# TSOC_GROVEY_WIFI_R1_1.net
KiCad netlist of a schematic drawn in EAGLE
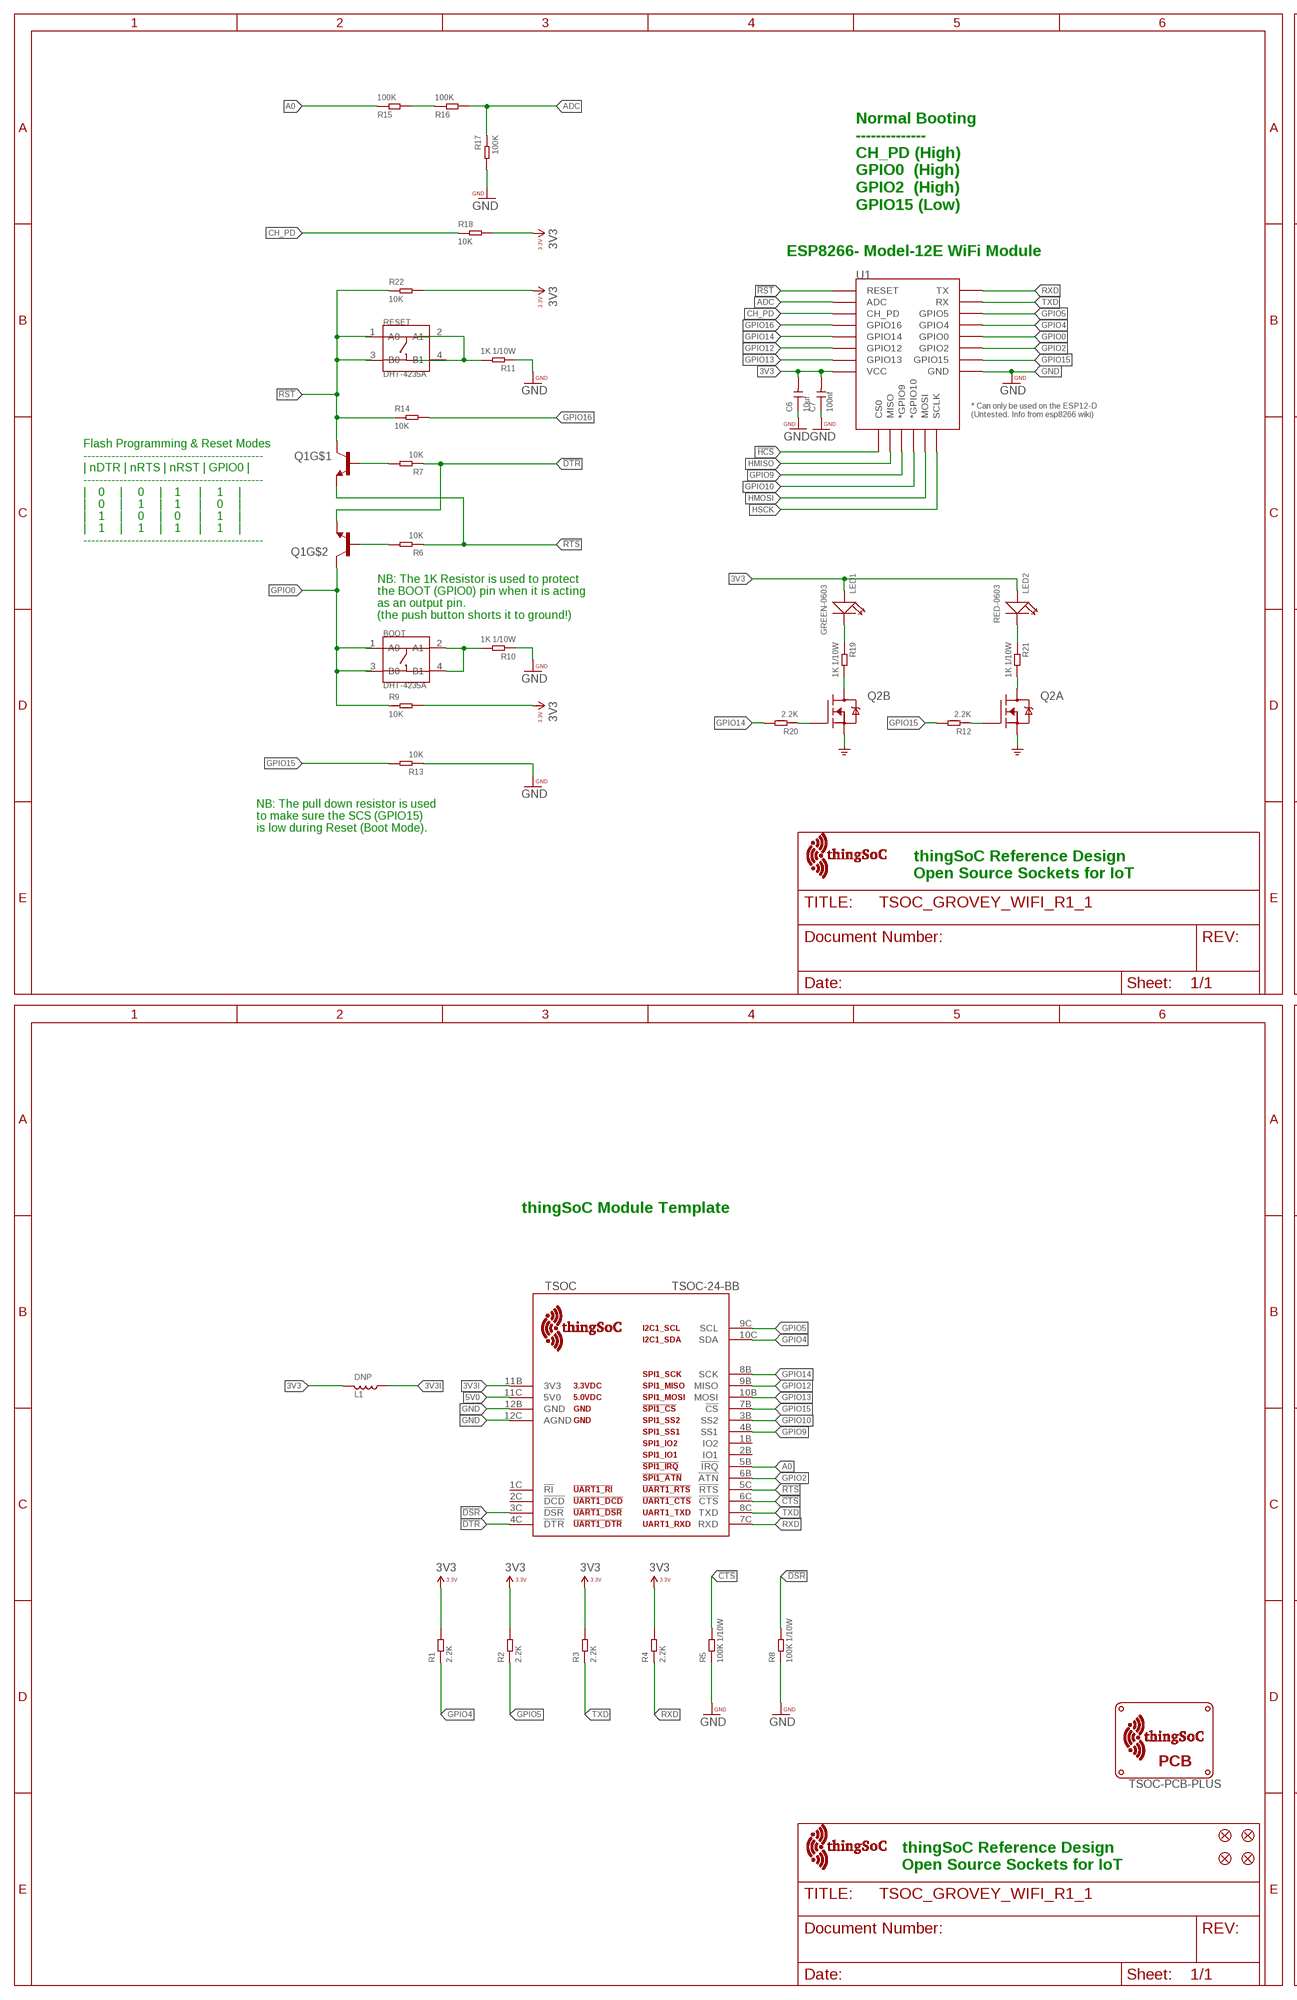
[diagram p0: schematic, sheet 1, part 1 of 2]
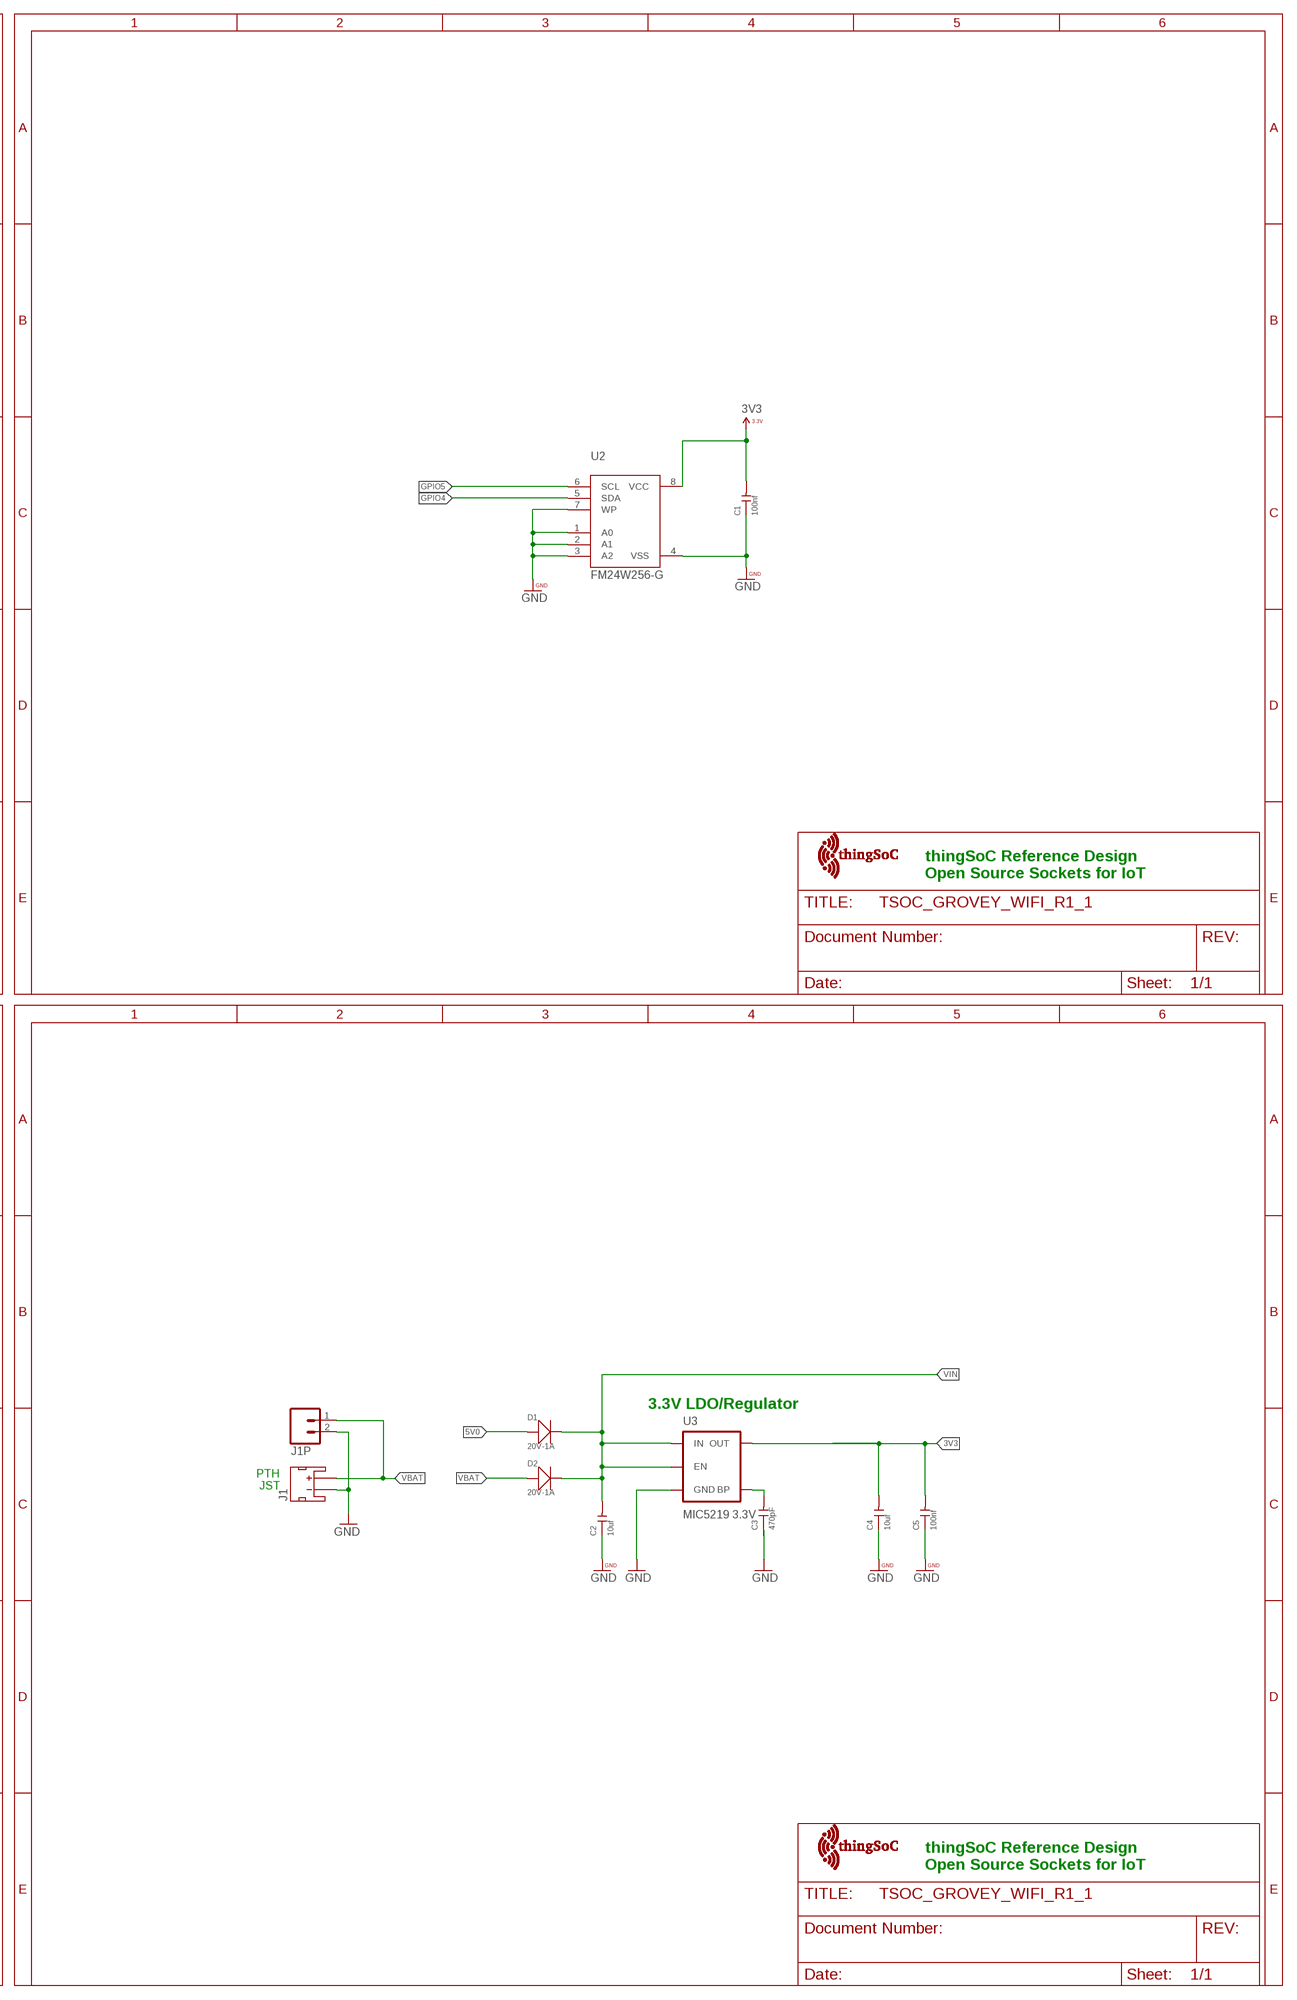
[diagram p1: schematic, sheet 1, part 2 of 2]

(export (version "E")
  (design (tool "Eeschema 10.0.6"))
  (components
    (comp (ref "$$U$1")
      (value "TSOC-LOGO-MED")
      (footprint "eagle-import:TSOC-LOGO-MED")
      (libsource (lib "eagle-import") (part "TSOC-LOGO-MED"))
    )
    (comp (ref "$$U$2")
      (value "TSOC-LOGO-MED")
      (footprint "eagle-import:TSOC-LOGO-MED")
      (libsource (lib "eagle-import") (part "TSOC-LOGO-MED"))
    )
    (comp (ref "BOOT")
      (value "DHT-4235A")
      (footprint "eagle-import:SW4-SMD-4.2X3.2X2.5MM")
      (libsource (lib "eagle-import") (part "SMD-BUTTON-TOP-DHT-4235A(4P-4.2X3.2MM)"))
    )
    (comp (ref "C1")
      (value "100nf")
      (footprint "eagle-import:C0603")
      (fields (field (name "MPN") "CC0603KRX7R9BB104"))
      (libsource (lib "eagle-import") (part "CERAMIC-100NF-50V-10%-X7R(0603)"))
    )
    (comp (ref "C2")
      (value "10uf")
      (footprint "eagle-import:C1206")
      (fields (field (name "MPN") "CC1206KKX5R8BB106"))
      (libsource (lib "eagle-import") (part "CERAMIC-10UF-25V-10%-X5R(1206)"))
    )
    (comp (ref "C3")
      (value "470pF")
      (footprint "eagle-import:C0603")
      (fields (field (name "MPN") "CC0603KRX7R9BB104"))
      (libsource (lib "eagle-import") (part "CERAMIC-100NF-50V-10%-X7R(0603)"))
    )
    (comp (ref "C4")
      (value "10uf")
      (footprint "eagle-import:C1206")
      (fields (field (name "MPN") "CC1206KKX5R8BB106"))
      (libsource (lib "eagle-import") (part "CERAMIC-10UF-25V-10%-X5R(1206)"))
    )
    (comp (ref "C5")
      (value "100nf")
      (footprint "eagle-import:C0603")
      (fields (field (name "MPN") "CC0603KRX7R9BB104"))
      (libsource (lib "eagle-import") (part "CERAMIC-100NF-50V-10%-X7R(0603)"))
    )
    (comp (ref "C6")
      (value "10uf")
      (footprint "eagle-import:C1206")
      (fields (field (name "MPN") "CC1206KKX5R8BB106"))
      (libsource (lib "eagle-import") (part "CERAMIC-10UF-25V-10%-X5R(1206)"))
    )
    (comp (ref "C7")
      (value "100nf")
      (footprint "eagle-import:C0603")
      (fields (field (name "MPN") "CC0603KRX7R9BB104"))
      (libsource (lib "eagle-import") (part "CERAMIC-100NF-50V-10%-X7R(0603)"))
    )
    (comp (ref "D1")
      (value "20V-1A")
      (footprint "eagle-import:SOD-123")
      (fields (field (name "MPN") "B5819W"))
      (libsource (lib "eagle-import") (part "SMD-DIODE-SCHOTTKY-20V-1A(SOD-123)"))
    )
    (comp (ref "D2")
      (value "20V-1A")
      (footprint "eagle-import:SOD-123")
      (fields (field (name "MPN") "B5819W"))
      (libsource (lib "eagle-import") (part "SMD-DIODE-SCHOTTKY-20V-1A(SOD-123)"))
    )
    (comp (ref "FID1")
      (value "FIDUCIALUFIDUCIAL")
      (footprint "eagle-import:MICRO-FIDUCIAL")
      (libsource (lib "eagle-import") (part "FIDUCIALUFIDUCIAL"))
    )
    (comp (ref "FID2")
      (value "FIDUCIALUFIDUCIAL")
      (footprint "eagle-import:MICRO-FIDUCIAL")
      (libsource (lib "eagle-import") (part "FIDUCIALUFIDUCIAL"))
    )
    (comp (ref "FID3")
      (value "FIDUCIALUFIDUCIAL")
      (footprint "eagle-import:MICRO-FIDUCIAL")
      (libsource (lib "eagle-import") (part "FIDUCIALUFIDUCIAL"))
    )
    (comp (ref "FID4")
      (value "FIDUCIALUFIDUCIAL")
      (footprint "eagle-import:MICRO-FIDUCIAL")
      (libsource (lib "eagle-import") (part "FIDUCIALUFIDUCIAL"))
    )
    (comp (ref "J1")
      (value "JST_2MM_MALE")
      (footprint "eagle-import:JST-2-SMD")
      (libsource (lib "eagle-import") (part "JST_2MM_MALE"))
    )
    (comp (ref "J1P")
      (value "M02-JST-2-PTH-NO_SILK")
      (footprint "eagle-import:JST-2-PTH-NS")
      (libsource (lib "eagle-import") (part "M02-JST-2-PTH-NO_SILK"))
    )
    (comp (ref "L1")
      (value "DNP")
      (footprint "eagle-import:L0603")
      (fields (field (name "MPN") "BLM18AG121SN1D"))
      (libsource (lib "eagle-import") (part "SMD-FERRITE-CHIP-120-OHM-500MA(0603)"))
    )
    (comp (ref "LED1")
      (value "GREEN-0603")
      (footprint "eagle-import:LED-0603")
      (fields (field (name "MPN") "19-217-G7C-AN1P2-3T"))
      (libsource (lib "eagle-import") (part "SMD-LED-CLEAR-GREEN(0603)"))
    )
    (comp (ref "LED2")
      (value "RED-0603")
      (footprint "eagle-import:LED-0603")
      (fields (field (name "MPN") "19-217-R6C-AL1M2VY-3T"))
      (libsource (lib "eagle-import") (part "LED-SMD-RED-DIFFUSED(0603)"))
    )
    (comp (ref "PCB")
      (value "TSOC-PCB-PLUS")
      (footprint "eagle-import:TSOC-BB-BRD-PLUS-DIM")
      (libsource (lib "eagle-import") (part "TSOC-PCB-PLUS"))
    )
    (comp (ref "Q1")
      (value "MMBT2222A")
      (footprint "eagle-import:SOT363")
      (libsource (lib "eagle-import") (part "MMDT3904"))
    )
    (comp (ref "Q2")
      (value "FDG1024NZ")
      (footprint "eagle-import:SOT95P280X110-6N")
      (libsource (lib "eagle-import") (part "FDG1024NZ"))
    )
    (comp (ref "R1")
      (value "2.2K")
      (footprint "eagle-import:R0603")
      (fields (field (name "MPN") "RC0603JR-072K2L"))
      (libsource (lib "eagle-import") (part "SMD-RES-2.2K-5%-1/10W(0603)"))
    )
    (comp (ref "R2")
      (value "2.2K")
      (footprint "eagle-import:R0603")
      (fields (field (name "MPN") "RC0603JR-072K2L"))
      (libsource (lib "eagle-import") (part "SMD-RES-2.2K-5%-1/10W(0603)"))
    )
    (comp (ref "R3")
      (value "2.2K")
      (footprint "eagle-import:R0603")
      (fields (field (name "MPN") "RC0603JR-072K2L"))
      (libsource (lib "eagle-import") (part "SMD-RES-2.2K-5%-1/10W(0603)"))
    )
    (comp (ref "R4")
      (value "2.2K")
      (footprint "eagle-import:R0603")
      (fields (field (name "MPN") "RC0603JR-072K2L"))
      (libsource (lib "eagle-import") (part "SMD-RES-2.2K-5%-1/10W(0603)"))
    )
    (comp (ref "R5")
      (value "100K 1/10W")
      (footprint "eagle-import:R0603")
      (fields (field (name "MPN") "RC0603JR-07100KL"))
      (libsource (lib "eagle-import") (part "SMD-RES-100K-5%-1/10W(0603)"))
    )
    (comp (ref "R6")
      (value "10K")
      (footprint "eagle-import:R0603")
      (fields (field (name "MPN") "RC0603FR-0710KL"))
      (libsource (lib "eagle-import") (part "SMD-RES-10K-1%-1/10W(0603)"))
    )
    (comp (ref "R7")
      (value "10K")
      (footprint "eagle-import:R0603")
      (fields (field (name "MPN") "RC0603FR-0710KL"))
      (libsource (lib "eagle-import") (part "SMD-RES-10K-1%-1/10W(0603)"))
    )
    (comp (ref "R8")
      (value "100K 1/10W")
      (footprint "eagle-import:R0603")
      (fields (field (name "MPN") "RC0603JR-07100KL"))
      (libsource (lib "eagle-import") (part "SMD-RES-100K-5%-1/10W(0603)"))
    )
    (comp (ref "R9")
      (value "10K")
      (footprint "eagle-import:R0603")
      (fields (field (name "MPN") "RC0603FR-0710KL"))
      (libsource (lib "eagle-import") (part "SMD-RES-10K-1%-1/10W(0603)"))
    )
    (comp (ref "R10")
      (value "1K 1/10W")
      (footprint "eagle-import:R0603")
      (fields (field (name "MPN") "RC0603JR-071KL"))
      (libsource (lib "eagle-import") (part "SMD-RES-1K-5%-1/10W(0603)"))
    )
    (comp (ref "R11")
      (value "1K 1/10W")
      (footprint "eagle-import:R0603")
      (fields (field (name "MPN") "RC0603JR-071KL"))
      (libsource (lib "eagle-import") (part "SMD-RES-1K-5%-1/10W(0603)"))
    )
    (comp (ref "R12")
      (value "2.2K")
      (footprint "eagle-import:R0603")
      (fields (field (name "MPN") "RC0603JR-072K2L"))
      (libsource (lib "eagle-import") (part "SMD-RES-2.2K-5%-1/10W(0603)"))
    )
    (comp (ref "R13")
      (value "10K")
      (footprint "eagle-import:R0603")
      (fields (field (name "MPN") "RC0603FR-0710KL"))
      (libsource (lib "eagle-import") (part "SMD-RES-10K-1%-1/10W(0603)"))
    )
    (comp (ref "R14")
      (value "10K")
      (footprint "eagle-import:R0603")
      (fields (field (name "MPN") "RC0603FR-0710KL"))
      (libsource (lib "eagle-import") (part "SMD-RES-10K-1%-1/10W(0603)"))
    )
    (comp (ref "R15")
      (value "100K")
      (footprint "eagle-import:R0603")
      (fields (field (name "MPN") "RC0603FR-07100KL"))
      (libsource (lib "eagle-import") (part "SMD-RES-100K-1%-1/10W(0603)"))
    )
    (comp (ref "R16")
      (value "100K")
      (footprint "eagle-import:R0603")
      (fields (field (name "MPN") "RC0603FR-07100KL"))
      (libsource (lib "eagle-import") (part "SMD-RES-100K-1%-1/10W(0603)"))
    )
    (comp (ref "R17")
      (value "100K")
      (footprint "eagle-import:R0603")
      (fields (field (name "MPN") "RC0603FR-07100KL"))
      (libsource (lib "eagle-import") (part "SMD-RES-100K-1%-1/10W(0603)"))
    )
    (comp (ref "R18")
      (value "10K")
      (footprint "eagle-import:R0603")
      (fields (field (name "MPN") "RC0603FR-0710KL"))
      (libsource (lib "eagle-import") (part "SMD-RES-10K-1%-1/10W(0603)"))
    )
    (comp (ref "R19")
      (value "1K 1/10W")
      (footprint "eagle-import:R0603")
      (fields (field (name "MPN") "RC0603JR-071KL"))
      (libsource (lib "eagle-import") (part "SMD-RES-1K-5%-1/10W(0603)"))
    )
    (comp (ref "R20")
      (value "2.2K")
      (footprint "eagle-import:R0603")
      (fields (field (name "MPN") "RC0603JR-072K2L"))
      (libsource (lib "eagle-import") (part "SMD-RES-2.2K-5%-1/10W(0603)"))
    )
    (comp (ref "R21")
      (value "1K 1/10W")
      (footprint "eagle-import:R0603")
      (fields (field (name "MPN") "RC0603JR-071KL"))
      (libsource (lib "eagle-import") (part "SMD-RES-1K-5%-1/10W(0603)"))
    )
    (comp (ref "R22")
      (value "10K")
      (footprint "eagle-import:R0603")
      (fields (field (name "MPN") "RC0603FR-0710KL"))
      (libsource (lib "eagle-import") (part "SMD-RES-10K-1%-1/10W(0603)"))
    )
    (comp (ref "RESET")
      (value "DHT-4235A")
      (footprint "eagle-import:SW4-SMD-4.2X3.2X2.5MM")
      (libsource (lib "eagle-import") (part "SMD-BUTTON-TOP-DHT-4235A(4P-4.2X3.2MM)"))
    )
    (comp (ref "TSOC")
      (value "TSOC-24-BB")
      (footprint "eagle-import:TSOC-BB-S24")
      (libsource (lib "eagle-import") (part "TSOC-24-BB"))
    )
    (comp (ref "U$101")
      (value "TSOC-LOGO-MED")
      (footprint "eagle-import:TSOC-LOGO-MED")
      (libsource (lib "eagle-import") (part "TSOC-LOGO-MED"))
    )
    (comp (ref "U$102")
      (value "TSOC-LOGO-MED")
      (footprint "eagle-import:TSOC-LOGO-MED")
      (libsource (lib "eagle-import") (part "TSOC-LOGO-MED"))
    )
    (comp (ref "U1")
      (value "ESP12ESMD")
      (footprint "eagle-import:ESP12E-SMD")
      (libsource (lib "eagle-import") (part "ESP12ESMD"))
    )
    (comp (ref "U2")
      (value "FM24W256-G")
      (footprint "eagle-import:SO08")
      (libsource (lib "eagle-import") (part "FM24W256-G"))
    )
    (comp (ref "U3")
      (value "MIC5219 3.3V")
      (footprint "eagle-import:SOT23-5")
      (libsource (lib "eagle-import") (part "V_REG_MIC52193.3V"))
    )
  )
  (nets
    (net (code "1") (name "/~{CTS}") (class "Default")
      (node (ref "R5") (pin "2") (pinfunction "2_2") (pintype "passive"))
      (node (ref "TSOC") (pin "6C") (pinfunction "~{CTS}_6C") (pintype "bidirectional"))
    )
    (net (code "2") (name "/~{DSR}") (class "Default")
      (node (ref "R8") (pin "2") (pinfunction "2_2") (pintype "passive"))
      (node (ref "TSOC") (pin "3C") (pinfunction "~{DSR}_3C") (pintype "bidirectional"))
    )
    (net (code "3") (name "/~{DTR}") (class "Default")
      (node (ref "Q1") (pin "1") (pinfunction "E_1") (pintype "passive"))
      (node (ref "R7") (pin "1") (pinfunction "1_1") (pintype "passive"))
      (node (ref "TSOC") (pin "4C") (pinfunction "~{DTR}_4C") (pintype "bidirectional"))
    )
    (net (code "4") (name "/~{HCS}") (class "Default")
      (node (ref "U1") (pin "CS0") (pinfunction "CS0_CS0") (pintype "bidirectional"))
    )
    (net (code "5") (name "/~{RST}") (class "Default")
      (node (ref "Q1") (pin "3") (pinfunction "C_3") (pintype "passive"))
      (node (ref "R14") (pin "1") (pinfunction "1_1") (pintype "passive"))
      (node (ref "R22") (pin "1") (pinfunction "1_1") (pintype "passive"))
      (node (ref "RESET") (pin "1") (pinfunction "A0_1") (pintype "bidirectional"))
      (node (ref "RESET") (pin "3") (pinfunction "B0_3") (pintype "bidirectional"))
      (node (ref "U1") (pin "RESET") (pinfunction "RESET_RESET") (pintype "bidirectional"))
    )
    (net (code "6") (name "/~{RTS}") (class "Default")
      (node (ref "Q1") (pin "4") (pinfunction "E_4") (pintype "passive"))
      (node (ref "R6") (pin "1") (pinfunction "1_1") (pintype "passive"))
      (node (ref "TSOC") (pin "5C") (pinfunction "~{RTS}_5C") (pintype "bidirectional"))
    )
    (net (code "7") (name "3V3") (class "Default")
      (node (ref "C1") (pin "2") (pinfunction "2_2") (pintype "passive"))
      (node (ref "C4") (pin "2") (pinfunction "2_2") (pintype "passive"))
      (node (ref "C5") (pin "2") (pinfunction "2_2") (pintype "passive"))
      (node (ref "C6") (pin "2") (pinfunction "2_2") (pintype "passive"))
      (node (ref "C7") (pin "2") (pinfunction "2_2") (pintype "passive"))
      (node (ref "L1") (pin "1") (pinfunction "1_1") (pintype "passive"))
      (node (ref "LED1") (pin "+") (pinfunction "+_+") (pintype "passive"))
      (node (ref "LED2") (pin "+") (pinfunction "+_+") (pintype "passive"))
      (node (ref "R1") (pin "2") (pinfunction "2_2") (pintype "passive"))
      (node (ref "R18") (pin "2") (pinfunction "2_2") (pintype "passive"))
      (node (ref "R2") (pin "2") (pinfunction "2_2") (pintype "passive"))
      (node (ref "R22") (pin "2") (pinfunction "2_2") (pintype "passive"))
      (node (ref "R3") (pin "2") (pinfunction "2_2") (pintype "passive"))
      (node (ref "R4") (pin "2") (pinfunction "2_2") (pintype "passive"))
      (node (ref "R9") (pin "2") (pinfunction "2_2") (pintype "passive"))
      (node (ref "U1") (pin "VCC") (pinfunction "VCC_VCC") (pintype "bidirectional"))
      (node (ref "U2") (pin "8") (pinfunction "VCC_8") (pintype "power_in"))
      (node (ref "U3") (pin "5") (pinfunction "OUT_5") (pintype "passive"))
    )
    (net (code "8") (name "3V3I") (class "Default")
      (node (ref "L1") (pin "2") (pinfunction "2_2") (pintype "passive"))
      (node (ref "TSOC") (pin "11B") (pinfunction "3V3_11B") (pintype "bidirectional"))
    )
    (net (code "9") (name "5V0") (class "Default")
      (node (ref "D1") (pin "+") (pinfunction "+_+") (pintype "passive"))
      (node (ref "TSOC") (pin "11C") (pinfunction "5V0_11C") (pintype "bidirectional"))
    )
    (net (code "10") (name "A0") (class "Default")
      (node (ref "R15") (pin "1") (pinfunction "1_1") (pintype "passive"))
      (node (ref "TSOC") (pin "5B") (pinfunction "~{IRQ}_5B") (pintype "bidirectional"))
    )
    (net (code "11") (name "ADC") (class "Default")
      (node (ref "R16") (pin "2") (pinfunction "2_2") (pintype "passive"))
      (node (ref "R17") (pin "1") (pinfunction "1_1") (pintype "passive"))
      (node (ref "U1") (pin "ADC") (pinfunction "ADC_ADC") (pintype "bidirectional"))
    )
    (net (code "12") (name "CH_PD") (class "Default")
      (node (ref "R18") (pin "1") (pinfunction "1_1") (pintype "passive"))
      (node (ref "U1") (pin "CH_PD") (pinfunction "CH_PD_CH_PD") (pintype "bidirectional"))
    )
    (net (code "13") (name "GND") (class "Default")
      (node (ref "C1") (pin "1") (pinfunction "1_1") (pintype "passive"))
      (node (ref "C2") (pin "1") (pinfunction "1_1") (pintype "passive"))
      (node (ref "C3") (pin "1") (pinfunction "1_1") (pintype "passive"))
      (node (ref "C4") (pin "1") (pinfunction "1_1") (pintype "passive"))
      (node (ref "C5") (pin "1") (pinfunction "1_1") (pintype "passive"))
      (node (ref "C6") (pin "1") (pinfunction "1_1") (pintype "passive"))
      (node (ref "C7") (pin "1") (pinfunction "1_1") (pintype "passive"))
      (node (ref "J1") (pin "1") (pinfunction "-_1") (pintype "bidirectional"))
      (node (ref "J1P") (pin "2") (pinfunction "2_2") (pintype "passive"))
      (node (ref "Q2") (pin "1") (pinfunction "S_1") (pintype "passive"))
      (node (ref "Q2") (pin "4") (pinfunction "S_4") (pintype "passive"))
      (node (ref "R10") (pin "1") (pinfunction "1_1") (pintype "passive"))
      (node (ref "R11") (pin "1") (pinfunction "1_1") (pintype "passive"))
      (node (ref "R13") (pin "1") (pinfunction "1_1") (pintype "passive"))
      (node (ref "R17") (pin "2") (pinfunction "2_2") (pintype "passive"))
      (node (ref "R5") (pin "1") (pinfunction "1_1") (pintype "passive"))
      (node (ref "R8") (pin "1") (pinfunction "1_1") (pintype "passive"))
      (node (ref "TSOC") (pin "12B") (pinfunction "GND_12B") (pintype "bidirectional"))
      (node (ref "TSOC") (pin "12C") (pinfunction "AGND_12C") (pintype "bidirectional"))
      (node (ref "U1") (pin "GND") (pinfunction "GND_GND") (pintype "bidirectional"))
      (node (ref "U2") (pin "1") (pinfunction "A0_1") (pintype "bidirectional"))
      (node (ref "U2") (pin "2") (pinfunction "A1_2") (pintype "bidirectional"))
      (node (ref "U2") (pin "3") (pinfunction "A2_3") (pintype "bidirectional"))
      (node (ref "U2") (pin "4") (pinfunction "VSS_4") (pintype "power_in"))
      (node (ref "U2") (pin "7") (pinfunction "WP_7") (pintype "bidirectional"))
      (node (ref "U3") (pin "2") (pinfunction "GND_2") (pintype "input"))
    )
    (net (code "14") (name "GPIO0") (class "Default")
      (node (ref "BOOT") (pin "1") (pinfunction "A0_1") (pintype "bidirectional"))
      (node (ref "BOOT") (pin "3") (pinfunction "B0_3") (pintype "bidirectional"))
      (node (ref "Q1") (pin "6") (pinfunction "C_6") (pintype "passive"))
      (node (ref "R9") (pin "1") (pinfunction "1_1") (pintype "passive"))
      (node (ref "U1") (pin "GPIO0") (pinfunction "GPIO0_GPIO0") (pintype "bidirectional"))
    )
    (net (code "15") (name "GPIO2") (class "Default")
      (node (ref "TSOC") (pin "6B") (pinfunction "~{ATN}_6B") (pintype "bidirectional"))
      (node (ref "U1") (pin "GPIO2") (pinfunction "GPIO2_GPIO2") (pintype "bidirectional"))
    )
    (net (code "16") (name "GPIO4") (class "Default")
      (node (ref "R1") (pin "1") (pinfunction "1_1") (pintype "passive"))
      (node (ref "TSOC") (pin "10C") (pinfunction "SDA_10C") (pintype "bidirectional"))
      (node (ref "U1") (pin "GPIO4") (pinfunction "GPIO4_GPIO4") (pintype "bidirectional"))
      (node (ref "U2") (pin "5") (pinfunction "SDA_5") (pintype "bidirectional"))
    )
    (net (code "17") (name "GPIO5") (class "Default")
      (node (ref "R2") (pin "1") (pinfunction "1_1") (pintype "passive"))
      (node (ref "TSOC") (pin "9C") (pinfunction "SCL_9C") (pintype "bidirectional"))
      (node (ref "U1") (pin "GPIO5") (pinfunction "GPIO5_GPIO5") (pintype "bidirectional"))
      (node (ref "U2") (pin "6") (pinfunction "SCL_6") (pintype "bidirectional"))
    )
    (net (code "18") (name "GPIO9") (class "Default")
      (node (ref "TSOC") (pin "4B") (pinfunction "SS1_4B") (pintype "bidirectional"))
      (node (ref "U1") (pin "GPIO9") (pinfunction "*GPIO9_GPIO9") (pintype "bidirectional"))
    )
    (net (code "19") (name "GPIO10") (class "Default")
      (node (ref "TSOC") (pin "3B") (pinfunction "SS2_3B") (pintype "bidirectional"))
      (node (ref "U1") (pin "GPIO10") (pinfunction "*GPIO10_GPIO10") (pintype "bidirectional"))
    )
    (net (code "20") (name "GPIO12") (class "Default")
      (node (ref "TSOC") (pin "9B") (pinfunction "MISO_9B") (pintype "bidirectional"))
      (node (ref "U1") (pin "GPIO12") (pinfunction "GPIO12_GPIO12") (pintype "bidirectional"))
    )
    (net (code "21") (name "GPIO13") (class "Default")
      (node (ref "TSOC") (pin "10B") (pinfunction "MOSI_10B") (pintype "bidirectional"))
      (node (ref "U1") (pin "GPIO13") (pinfunction "GPIO13_GPIO13") (pintype "bidirectional"))
    )
    (net (code "22") (name "GPIO14") (class "Default")
      (node (ref "R20") (pin "2") (pinfunction "2_2") (pintype "passive"))
      (node (ref "TSOC") (pin "8B") (pinfunction "SCK_8B") (pintype "bidirectional"))
      (node (ref "U1") (pin "GPIO14") (pinfunction "GPIO14_GPIO14") (pintype "bidirectional"))
    )
    (net (code "23") (name "GPIO15") (class "Default")
      (node (ref "R12") (pin "2") (pinfunction "2_2") (pintype "passive"))
      (node (ref "R13") (pin "2") (pinfunction "2_2") (pintype "passive"))
      (node (ref "TSOC") (pin "7B") (pinfunction "~{CS}_7B") (pintype "bidirectional"))
      (node (ref "U1") (pin "GPIO15") (pinfunction "GPIO15_GPIO15") (pintype "bidirectional"))
    )
    (net (code "24") (name "GPIO16") (class "Default")
      (node (ref "R14") (pin "2") (pinfunction "2_2") (pintype "passive"))
      (node (ref "U1") (pin "GPIO16") (pinfunction "GPIO16_GPIO16") (pintype "bidirectional"))
    )
    (net (code "25") (name "HMISO") (class "Default")
      (node (ref "U1") (pin "MISO") (pinfunction "MISO_MISO") (pintype "bidirectional"))
    )
    (net (code "26") (name "HMOSI") (class "Default")
      (node (ref "U1") (pin "MOSI") (pinfunction "MOSI_MOSI") (pintype "bidirectional"))
    )
    (net (code "27") (name "HSCK") (class "Default")
      (node (ref "U1") (pin "SCLK") (pinfunction "SCLK_SCLK") (pintype "bidirectional"))
    )
    (net (code "28") (name "Net-(BOOT-A1)") (class "Default")
      (node (ref "BOOT") (pin "2") (pinfunction "A1_2") (pintype "bidirectional"))
      (node (ref "BOOT") (pin "4") (pinfunction "B1_4") (pintype "bidirectional"))
      (node (ref "R10") (pin "2") (pinfunction "2_2") (pintype "passive"))
    )
    (net (code "29") (name "Net-(LED1-Pad-)") (class "Default")
      (node (ref "LED1") (pin "-") (pinfunction "-_-") (pintype "passive"))
      (node (ref "R19") (pin "1") (pinfunction "1_1") (pintype "passive"))
    )
    (net (code "30") (name "Net-(LED2-Pad-)") (class "Default")
      (node (ref "LED2") (pin "-") (pinfunction "-_-") (pintype "passive"))
      (node (ref "R21") (pin "1") (pinfunction "1_1") (pintype "passive"))
    )
    (net (code "31") (name "Net-(Q1A-B)") (class "Default")
      (node (ref "Q1") (pin "5") (pinfunction "B_5") (pintype "passive"))
      (node (ref "R7") (pin "2") (pinfunction "2_2") (pintype "passive"))
    )
    (net (code "32") (name "Net-(Q1B-B)") (class "Default")
      (node (ref "Q1") (pin "2") (pinfunction "B_2") (pintype "passive"))
      (node (ref "R6") (pin "2") (pinfunction "2_2") (pintype "passive"))
    )
    (net (code "33") (name "Net-(Q2A-D)") (class "Default")
      (node (ref "Q2") (pin "6") (pinfunction "D_6") (pintype "passive"))
      (node (ref "R21") (pin "2") (pinfunction "2_2") (pintype "passive"))
    )
    (net (code "34") (name "Net-(Q2A-G)") (class "Default")
      (node (ref "Q2") (pin "2") (pinfunction "G_2") (pintype "passive"))
      (node (ref "R12") (pin "1") (pinfunction "1_1") (pintype "passive"))
    )
    (net (code "35") (name "Net-(Q2B-D)") (class "Default")
      (node (ref "Q2") (pin "3") (pinfunction "D_3") (pintype "passive"))
      (node (ref "R19") (pin "2") (pinfunction "2_2") (pintype "passive"))
    )
    (net (code "36") (name "Net-(Q2B-G)") (class "Default")
      (node (ref "Q2") (pin "5") (pinfunction "G_5") (pintype "passive"))
      (node (ref "R20") (pin "1") (pinfunction "1_1") (pintype "passive"))
    )
    (net (code "37") (name "Net-(R15-Pad2)") (class "Default")
      (node (ref "R15") (pin "2") (pinfunction "2_2") (pintype "passive"))
      (node (ref "R16") (pin "1") (pinfunction "1_1") (pintype "passive"))
    )
    (net (code "38") (name "Net-(RESET-A1)") (class "Default")
      (node (ref "R11") (pin "2") (pinfunction "2_2") (pintype "passive"))
      (node (ref "RESET") (pin "2") (pinfunction "A1_2") (pintype "bidirectional"))
      (node (ref "RESET") (pin "4") (pinfunction "B1_4") (pintype "bidirectional"))
    )
    (net (code "39") (name "Net-(U3-BP)") (class "Default")
      (node (ref "C3") (pin "2") (pinfunction "2_2") (pintype "passive"))
      (node (ref "U3") (pin "4") (pinfunction "BP_4") (pintype "input"))
    )
    (net (code "40") (name "RXD") (class "Default")
      (node (ref "R4") (pin "1") (pinfunction "1_1") (pintype "passive"))
      (node (ref "TSOC") (pin "7C") (pinfunction "RXD_7C") (pintype "bidirectional"))
      (node (ref "U1") (pin "TXD0") (pinfunction "TX_TXD0") (pintype "bidirectional"))
    )
    (net (code "41") (name "TXD") (class "Default")
      (node (ref "R3") (pin "1") (pinfunction "1_1") (pintype "passive"))
      (node (ref "TSOC") (pin "8C") (pinfunction "TXD_8C") (pintype "bidirectional"))
      (node (ref "U1") (pin "RXD0") (pinfunction "RX_RXD0") (pintype "bidirectional"))
    )
    (net (code "42") (name "VBAT") (class "Default")
      (node (ref "D2") (pin "+") (pinfunction "+_+") (pintype "passive"))
      (node (ref "J1") (pin "2") (pinfunction "+_2") (pintype "bidirectional"))
      (node (ref "J1P") (pin "1") (pinfunction "1_1") (pintype "passive"))
    )
    (net (code "43") (name "VIN") (class "Default")
      (node (ref "C2") (pin "2") (pinfunction "2_2") (pintype "passive"))
      (node (ref "D1") (pin "-") (pinfunction "-_-") (pintype "passive"))
      (node (ref "D2") (pin "-") (pinfunction "-_-") (pintype "passive"))
      (node (ref "U3") (pin "1") (pinfunction "IN_1") (pintype "input"))
      (node (ref "U3") (pin "3") (pinfunction "EN_3") (pintype "input"))
    )
    (net (code "44") (name "unconnected-(J1-PAD1-PadNC1)") (class "Default")
      (node (ref "J1") (pin "NC1") (pinfunction "PAD1_NC1") (pintype "bidirectional"))
    )
    (net (code "45") (name "unconnected-(J1-PAD2-PadNC2)") (class "Default")
      (node (ref "J1") (pin "NC2") (pinfunction "PAD2_NC2") (pintype "bidirectional"))
    )
    (net (code "46") (name "unconnected-(TSOC-IO1-Pad2B)") (class "Default")
      (node (ref "TSOC") (pin "2B") (pinfunction "IO1_2B") (pintype "bidirectional"))
    )
    (net (code "47") (name "unconnected-(TSOC-IO2-Pad1B)") (class "Default")
      (node (ref "TSOC") (pin "1B") (pinfunction "IO2_1B") (pintype "bidirectional"))
    )
    (net (code "48") (name "unconnected-(TSOC-~{DCD}-Pad2C)") (class "Default")
      (node (ref "TSOC") (pin "2C") (pinfunction "~{DCD}_2C") (pintype "bidirectional"))
    )
    (net (code "49") (name "unconnected-(TSOC-~{RI}-Pad1C)") (class "Default")
      (node (ref "TSOC") (pin "1C") (pinfunction "~{RI}_1C") (pintype "bidirectional"))
    )
  )
)
